# analog_filters.net
KiCad netlist of a schematic drawn in Altium Designer
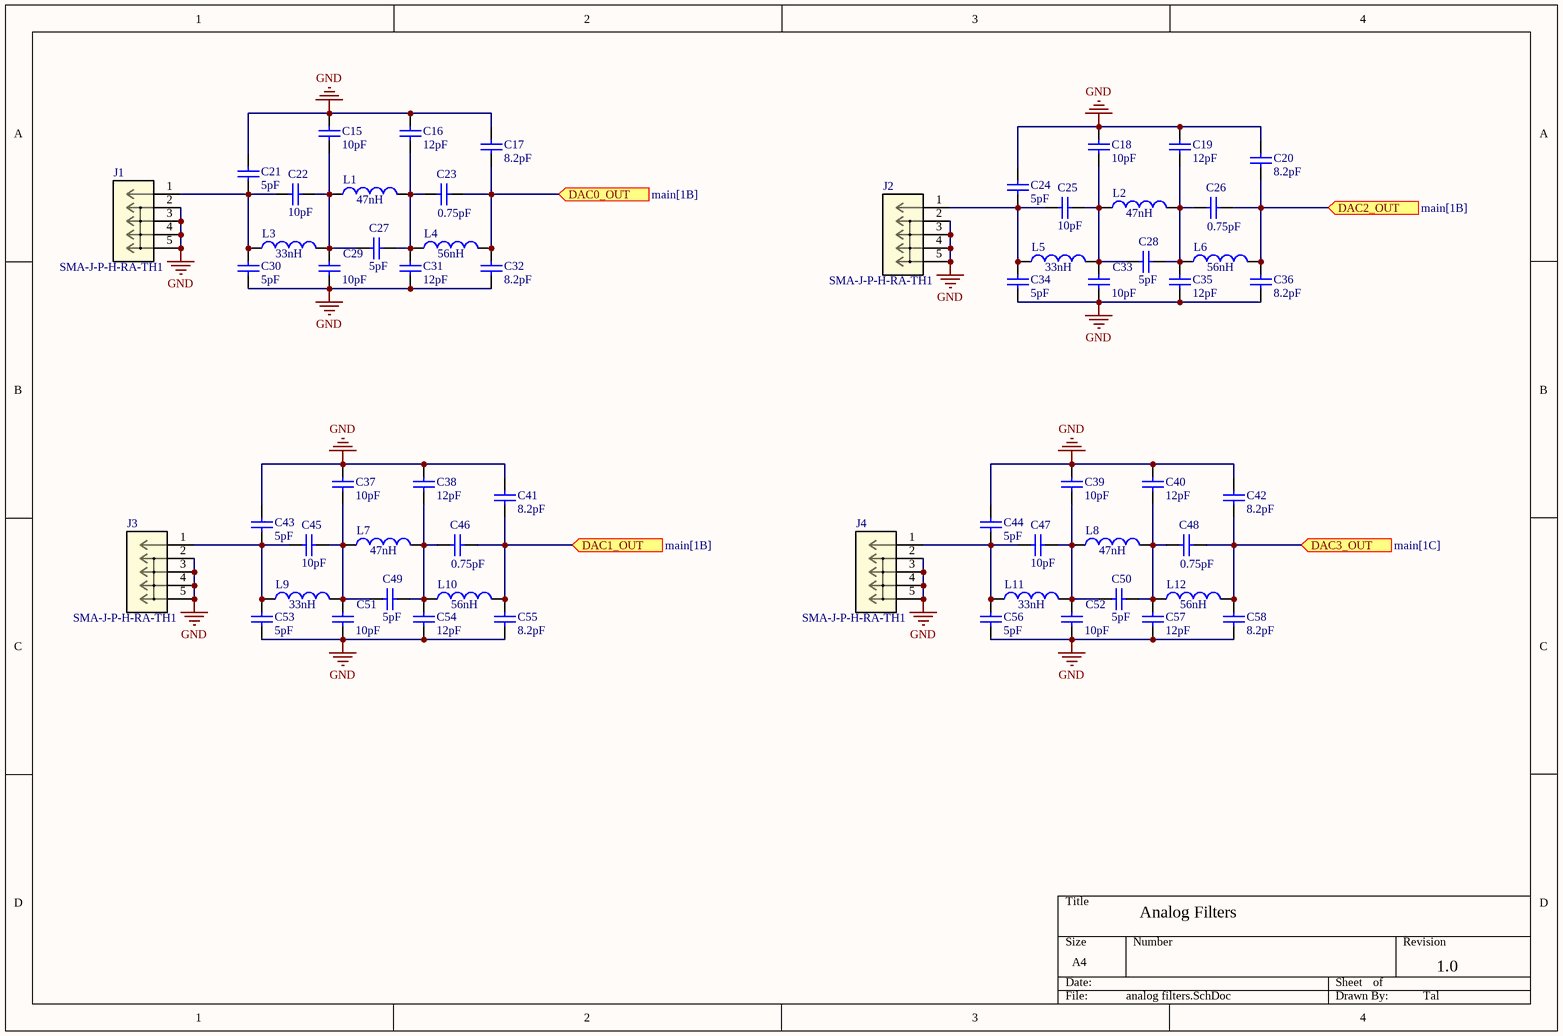
[diagram p0: analog filters.SchDoc]

(export (version "E")
  (design (tool "Eeschema 10.0.6"))
  (components
    (comp (ref "C15")
      (value "10pF 50V")
      (footprint "Landa_PCB:C0402")
      (description "CAP CER 10PF 50V 5% NP0 0402")
      (fields
        (field (name "MANUFACTURER") "TDK Corporation")
        (field (name "MANUFACTURER PART NUMBER") "C1005C0G1H200J")
        (field (name "CAPACITANCE") "10pF")
      )
      (libsource (lib "L_SCH_C") (part "CAP CER 20pF 50V 5% NP0 0402"))
    )
    (comp (ref "C16")
      (value "12pF 50V")
      (footprint "Landa_PCB:C0402")
      (description "CAP CER 12PF 50V 5% NP0 0402")
      (fields
        (field (name "MANUFACTURER") "TDK Corporation")
        (field (name "MANUFACTURER PART NUMBER") "C1005C0G1H200J")
        (field (name "CAPACITANCE") "12pF")
      )
      (libsource (lib "L_SCH_C") (part "CAP CER 20pF 50V 5% NP0 0402"))
    )
    (comp (ref "C17")
      (value "8.2pF 50V")
      (footprint "Landa_PCB:C0402")
      (description "CAP CER 8.2PF 50V 5% NP0 0402")
      (fields
        (field (name "MANUFACTURER") "TDK Corporation")
        (field (name "MANUFACTURER PART NUMBER") "C1005C0G1H200J")
        (field (name "CAPACITANCE") "8.2pF")
      )
      (libsource (lib "L_SCH_C") (part "CAP CER 20pF 50V 5% NP0 0402"))
    )
    (comp (ref "C18")
      (value "10pF 50V")
      (footprint "Landa_PCB:C0402")
      (description "CAP CER 10PF 50V 5% NP0 0402")
      (fields
        (field (name "MANUFACTURER") "TDK Corporation")
        (field (name "MANUFACTURER PART NUMBER") "C1005C0G1H200J")
        (field (name "CAPACITANCE") "10pF")
      )
      (libsource (lib "L_SCH_C") (part "CAP CER 20pF 50V 5% NP0 0402"))
    )
    (comp (ref "C19")
      (value "12pF 50V")
      (footprint "Landa_PCB:C0402")
      (description "CAP CER 12PF 50V 5% NP0 0402")
      (fields
        (field (name "MANUFACTURER") "TDK Corporation")
        (field (name "MANUFACTURER PART NUMBER") "C1005C0G1H200J")
        (field (name "CAPACITANCE") "12pF")
      )
      (libsource (lib "L_SCH_C") (part "CAP CER 20pF 50V 5% NP0 0402"))
    )
    (comp (ref "C20")
      (value "8.2pF 50V")
      (footprint "Landa_PCB:C0402")
      (description "CAP CER 8.2PF 50V 5% NP0 0402")
      (fields
        (field (name "MANUFACTURER") "TDK Corporation")
        (field (name "MANUFACTURER PART NUMBER") "C1005C0G1H200J")
        (field (name "CAPACITANCE") "8.2pF")
      )
      (libsource (lib "L_SCH_C") (part "CAP CER 20pF 50V 5% NP0 0402"))
    )
    (comp (ref "C21")
      (value "5pF 50V")
      (footprint "Landa_PCB:C0402")
      (description "CAP CER 5PF 50V 5% NP0 0402")
      (fields
        (field (name "MANUFACTURER") "TDK Corporation")
        (field (name "MANUFACTURER PART NUMBER") "C1005C0G1H200J")
        (field (name "CAPACITANCE") "5pF")
      )
      (libsource (lib "L_SCH_C") (part "CAP CER 20pF 50V 5% NP0 0402"))
    )
    (comp (ref "C22")
      (value "10pF 50V")
      (footprint "Landa_PCB:C0402")
      (description "CAP CER 10PF 50V 5% NP0 0402")
      (fields
        (field (name "MANUFACTURER") "TDK Corporation")
        (field (name "MANUFACTURER PART NUMBER") "C1005C0G1H200J")
        (field (name "CAPACITANCE") "10pF")
      )
      (libsource (lib "L_SCH_C") (part "CAP CER 20pF 50V 5% NP0 0402"))
    )
    (comp (ref "C23")
      (value "0.75pF 50V")
      (footprint "Landa_PCB:C0402")
      (description "CAP CER 0.75PF 50V 5% NP0 0402")
      (fields
        (field (name "MANUFACTURER") "TDK Corporation")
        (field (name "MANUFACTURER PART NUMBER") "C1005C0G1H200J")
        (field (name "CAPACITANCE") "0.75pF")
      )
      (libsource (lib "L_SCH_C") (part "CAP CER 20pF 50V 5% NP0 0402"))
    )
    (comp (ref "C24")
      (value "5pF 50V")
      (footprint "Landa_PCB:C0402")
      (description "CAP CER 5PF 50V 5% NP0 0402")
      (fields
        (field (name "MANUFACTURER") "TDK Corporation")
        (field (name "MANUFACTURER PART NUMBER") "C1005C0G1H200J")
        (field (name "CAPACITANCE") "5pF")
      )
      (libsource (lib "L_SCH_C") (part "CAP CER 20pF 50V 5% NP0 0402"))
    )
    (comp (ref "C25")
      (value "10pF 50V")
      (footprint "Landa_PCB:C0402")
      (description "CAP CER 10PF 50V 5% NP0 0402")
      (fields
        (field (name "MANUFACTURER") "TDK Corporation")
        (field (name "MANUFACTURER PART NUMBER") "C1005C0G1H200J")
        (field (name "CAPACITANCE") "10pF")
      )
      (libsource (lib "L_SCH_C") (part "CAP CER 20pF 50V 5% NP0 0402"))
    )
    (comp (ref "C26")
      (value "0.75pF 50V")
      (footprint "Landa_PCB:C0402")
      (description "CAP CER 0.75PF 50V 5% NP0 0402")
      (fields
        (field (name "MANUFACTURER") "TDK Corporation")
        (field (name "MANUFACTURER PART NUMBER") "C1005C0G1H200J")
        (field (name "CAPACITANCE") "0.75pF")
      )
      (libsource (lib "L_SCH_C") (part "CAP CER 20pF 50V 5% NP0 0402"))
    )
    (comp (ref "C27")
      (value "5pF 50V")
      (footprint "Landa_PCB:C0402")
      (description "CAP CER 5PF 50V 5% NP0 0402")
      (fields
        (field (name "MANUFACTURER") "TDK Corporation")
        (field (name "MANUFACTURER PART NUMBER") "C1005C0G1H200J")
        (field (name "CAPACITANCE") "5pF")
      )
      (libsource (lib "L_SCH_C") (part "CAP CER 20pF 50V 5% NP0 0402"))
    )
    (comp (ref "C28")
      (value "5pF 50V")
      (footprint "Landa_PCB:C0402")
      (description "CAP CER 5PF 50V 5% NP0 0402")
      (fields
        (field (name "MANUFACTURER") "TDK Corporation")
        (field (name "MANUFACTURER PART NUMBER") "C1005C0G1H200J")
        (field (name "CAPACITANCE") "5pF")
      )
      (libsource (lib "L_SCH_C") (part "CAP CER 20pF 50V 5% NP0 0402"))
    )
    (comp (ref "C29")
      (value "10pF 50V")
      (footprint "Landa_PCB:C0402")
      (description "CAP CER 10PF 50V 5% NP0 0402")
      (fields
        (field (name "MANUFACTURER") "TDK Corporation")
        (field (name "MANUFACTURER PART NUMBER") "C1005C0G1H200J")
        (field (name "CAPACITANCE") "10pF")
      )
      (libsource (lib "L_SCH_C") (part "CAP CER 20pF 50V 5% NP0 0402"))
    )
    (comp (ref "C30")
      (value "5pF 50V")
      (footprint "Landa_PCB:C0402")
      (description "CAP CER 5PF 50V 5% NP0 0402")
      (fields
        (field (name "MANUFACTURER") "TDK Corporation")
        (field (name "MANUFACTURER PART NUMBER") "C1005C0G1H200J")
        (field (name "CAPACITANCE") "5pF")
      )
      (libsource (lib "L_SCH_C") (part "CAP CER 20pF 50V 5% NP0 0402"))
    )
    (comp (ref "C31")
      (value "12pF 50V")
      (footprint "Landa_PCB:C0402")
      (description "CAP CER 12PF 50V 5% NP0 0402")
      (fields
        (field (name "MANUFACTURER") "TDK Corporation")
        (field (name "MANUFACTURER PART NUMBER") "C1005C0G1H200J")
        (field (name "CAPACITANCE") "12pF")
      )
      (libsource (lib "L_SCH_C") (part "CAP CER 20pF 50V 5% NP0 0402"))
    )
    (comp (ref "C32")
      (value "8.2pF 50V")
      (footprint "Landa_PCB:C0402")
      (description "CAP CER 8.2PF 50V 5% NP0 0402")
      (fields
        (field (name "MANUFACTURER") "TDK Corporation")
        (field (name "MANUFACTURER PART NUMBER") "C1005C0G1H200J")
        (field (name "CAPACITANCE") "8.2pF")
      )
      (libsource (lib "L_SCH_C") (part "CAP CER 20pF 50V 5% NP0 0402"))
    )
    (comp (ref "C33")
      (value "10pF 50V")
      (footprint "Landa_PCB:C0402")
      (description "CAP CER 10PF 50V 5% NP0 0402")
      (fields
        (field (name "MANUFACTURER") "TDK Corporation")
        (field (name "MANUFACTURER PART NUMBER") "C1005C0G1H200J")
        (field (name "CAPACITANCE") "10pF")
      )
      (libsource (lib "L_SCH_C") (part "CAP CER 20pF 50V 5% NP0 0402"))
    )
    (comp (ref "C34")
      (value "5pF 50V")
      (footprint "Landa_PCB:C0402")
      (description "CAP CER 5PF 50V 5% NP0 0402")
      (fields
        (field (name "MANUFACTURER") "TDK Corporation")
        (field (name "MANUFACTURER PART NUMBER") "C1005C0G1H200J")
        (field (name "CAPACITANCE") "5pF")
      )
      (libsource (lib "L_SCH_C") (part "CAP CER 20pF 50V 5% NP0 0402"))
    )
    (comp (ref "C35")
      (value "12pF 50V")
      (footprint "Landa_PCB:C0402")
      (description "CAP CER 12PF 50V 5% NP0 0402")
      (fields
        (field (name "MANUFACTURER") "TDK Corporation")
        (field (name "MANUFACTURER PART NUMBER") "C1005C0G1H200J")
        (field (name "CAPACITANCE") "12pF")
      )
      (libsource (lib "L_SCH_C") (part "CAP CER 20pF 50V 5% NP0 0402"))
    )
    (comp (ref "C36")
      (value "8.2pF 50V")
      (footprint "Landa_PCB:C0402")
      (description "CAP CER 8.2PF 50V 5% NP0 0402")
      (fields
        (field (name "MANUFACTURER") "TDK Corporation")
        (field (name "MANUFACTURER PART NUMBER") "C1005C0G1H200J")
        (field (name "CAPACITANCE") "8.2pF")
      )
      (libsource (lib "L_SCH_C") (part "CAP CER 20pF 50V 5% NP0 0402"))
    )
    (comp (ref "C37")
      (value "10pF 50V")
      (footprint "Landa_PCB:C0402")
      (description "CAP CER 10PF 50V 5% NP0 0402")
      (fields
        (field (name "MANUFACTURER") "TDK Corporation")
        (field (name "MANUFACTURER PART NUMBER") "C1005C0G1H200J")
        (field (name "CAPACITANCE") "10pF")
      )
      (libsource (lib "L_SCH_C") (part "CAP CER 20pF 50V 5% NP0 0402"))
    )
    (comp (ref "C38")
      (value "12pF 50V")
      (footprint "Landa_PCB:C0402")
      (description "CAP CER 12PF 50V 5% NP0 0402")
      (fields
        (field (name "MANUFACTURER") "TDK Corporation")
        (field (name "MANUFACTURER PART NUMBER") "C1005C0G1H200J")
        (field (name "CAPACITANCE") "12pF")
      )
      (libsource (lib "L_SCH_C") (part "CAP CER 20pF 50V 5% NP0 0402"))
    )
    (comp (ref "C39")
      (value "10pF 50V")
      (footprint "Landa_PCB:C0402")
      (description "CAP CER 10PF 50V 5% NP0 0402")
      (fields
        (field (name "MANUFACTURER") "TDK Corporation")
        (field (name "MANUFACTURER PART NUMBER") "C1005C0G1H200J")
        (field (name "CAPACITANCE") "10pF")
      )
      (libsource (lib "L_SCH_C") (part "CAP CER 20pF 50V 5% NP0 0402"))
    )
    (comp (ref "C40")
      (value "12pF 50V")
      (footprint "Landa_PCB:C0402")
      (description "CAP CER 12PF 50V 5% NP0 0402")
      (fields
        (field (name "MANUFACTURER") "TDK Corporation")
        (field (name "MANUFACTURER PART NUMBER") "C1005C0G1H200J")
        (field (name "CAPACITANCE") "12pF")
      )
      (libsource (lib "L_SCH_C") (part "CAP CER 20pF 50V 5% NP0 0402"))
    )
    (comp (ref "C41")
      (value "8.2pF 50V")
      (footprint "Landa_PCB:C0402")
      (description "CAP CER 8.2PF 50V 5% NP0 0402")
      (fields
        (field (name "MANUFACTURER") "TDK Corporation")
        (field (name "MANUFACTURER PART NUMBER") "C1005C0G1H200J")
        (field (name "CAPACITANCE") "8.2pF")
      )
      (libsource (lib "L_SCH_C") (part "CAP CER 20pF 50V 5% NP0 0402"))
    )
    (comp (ref "C42")
      (value "8.2pF 50V")
      (footprint "Landa_PCB:C0402")
      (description "CAP CER 8.2PF 50V 5% NP0 0402")
      (fields
        (field (name "MANUFACTURER") "TDK Corporation")
        (field (name "MANUFACTURER PART NUMBER") "C1005C0G1H200J")
        (field (name "CAPACITANCE") "8.2pF")
      )
      (libsource (lib "L_SCH_C") (part "CAP CER 20pF 50V 5% NP0 0402"))
    )
    (comp (ref "C43")
      (value "5pF 50V")
      (footprint "Landa_PCB:C0402")
      (description "CAP CER 5PF 50V 5% NP0 0402")
      (fields
        (field (name "MANUFACTURER") "TDK Corporation")
        (field (name "MANUFACTURER PART NUMBER") "C1005C0G1H200J")
        (field (name "CAPACITANCE") "5pF")
      )
      (libsource (lib "L_SCH_C") (part "CAP CER 20pF 50V 5% NP0 0402"))
    )
    (comp (ref "C44")
      (value "5pF 50V")
      (footprint "Landa_PCB:C0402")
      (description "CAP CER 5PF 50V 5% NP0 0402")
      (fields
        (field (name "MANUFACTURER") "TDK Corporation")
        (field (name "MANUFACTURER PART NUMBER") "C1005C0G1H200J")
        (field (name "CAPACITANCE") "5pF")
      )
      (libsource (lib "L_SCH_C") (part "CAP CER 20pF 50V 5% NP0 0402"))
    )
    (comp (ref "C45")
      (value "10pF 50V")
      (footprint "Landa_PCB:C0402")
      (description "CAP CER 10PF 50V 5% NP0 0402")
      (fields
        (field (name "MANUFACTURER") "TDK Corporation")
        (field (name "MANUFACTURER PART NUMBER") "C1005C0G1H200J")
        (field (name "CAPACITANCE") "10pF")
      )
      (libsource (lib "L_SCH_C") (part "CAP CER 20pF 50V 5% NP0 0402"))
    )
    (comp (ref "C46")
      (value "0.75pF 50V")
      (footprint "Landa_PCB:C0402")
      (description "CAP CER 0.75PF 50V 5% NP0 0402")
      (fields
        (field (name "MANUFACTURER") "TDK Corporation")
        (field (name "MANUFACTURER PART NUMBER") "C1005C0G1H200J")
        (field (name "CAPACITANCE") "0.75pF")
      )
      (libsource (lib "L_SCH_C") (part "CAP CER 20pF 50V 5% NP0 0402"))
    )
    (comp (ref "C47")
      (value "10pF 50V")
      (footprint "Landa_PCB:C0402")
      (description "CAP CER 10PF 50V 5% NP0 0402")
      (fields
        (field (name "MANUFACTURER") "TDK Corporation")
        (field (name "MANUFACTURER PART NUMBER") "C1005C0G1H200J")
        (field (name "CAPACITANCE") "10pF")
      )
      (libsource (lib "L_SCH_C") (part "CAP CER 20pF 50V 5% NP0 0402"))
    )
    (comp (ref "C48")
      (value "0.75pF 50V")
      (footprint "Landa_PCB:C0402")
      (description "CAP CER 0.75PF 50V 5% NP0 0402")
      (fields
        (field (name "MANUFACTURER") "TDK Corporation")
        (field (name "MANUFACTURER PART NUMBER") "C1005C0G1H200J")
        (field (name "CAPACITANCE") "0.75pF")
      )
      (libsource (lib "L_SCH_C") (part "CAP CER 20pF 50V 5% NP0 0402"))
    )
    (comp (ref "C49")
      (value "5pF 50V")
      (footprint "Landa_PCB:C0402")
      (description "CAP CER 5PF 50V 5% NP0 0402")
      (fields
        (field (name "MANUFACTURER") "TDK Corporation")
        (field (name "MANUFACTURER PART NUMBER") "C1005C0G1H200J")
        (field (name "CAPACITANCE") "5pF")
      )
      (libsource (lib "L_SCH_C") (part "CAP CER 20pF 50V 5% NP0 0402"))
    )
    (comp (ref "C50")
      (value "5pF 50V")
      (footprint "Landa_PCB:C0402")
      (description "CAP CER 5PF 50V 5% NP0 0402")
      (fields
        (field (name "MANUFACTURER") "TDK Corporation")
        (field (name "MANUFACTURER PART NUMBER") "C1005C0G1H200J")
        (field (name "CAPACITANCE") "5pF")
      )
      (libsource (lib "L_SCH_C") (part "CAP CER 20pF 50V 5% NP0 0402"))
    )
    (comp (ref "C51")
      (value "10pF 50V")
      (footprint "Landa_PCB:C0402")
      (description "CAP CER 10PF 50V 5% NP0 0402")
      (fields
        (field (name "MANUFACTURER") "TDK Corporation")
        (field (name "MANUFACTURER PART NUMBER") "C1005C0G1H200J")
        (field (name "CAPACITANCE") "10pF")
      )
      (libsource (lib "L_SCH_C") (part "CAP CER 20pF 50V 5% NP0 0402"))
    )
    (comp (ref "C52")
      (value "10pF 50V")
      (footprint "Landa_PCB:C0402")
      (description "CAP CER 10PF 50V 5% NP0 0402")
      (fields
        (field (name "MANUFACTURER") "TDK Corporation")
        (field (name "MANUFACTURER PART NUMBER") "C1005C0G1H200J")
        (field (name "CAPACITANCE") "10pF")
      )
      (libsource (lib "L_SCH_C") (part "CAP CER 20pF 50V 5% NP0 0402"))
    )
    (comp (ref "C53")
      (value "5pF 50V")
      (footprint "Landa_PCB:C0402")
      (description "CAP CER 5PF 50V 5% NP0 0402")
      (fields
        (field (name "MANUFACTURER") "TDK Corporation")
        (field (name "MANUFACTURER PART NUMBER") "C1005C0G1H200J")
        (field (name "CAPACITANCE") "5pF")
      )
      (libsource (lib "L_SCH_C") (part "CAP CER 20pF 50V 5% NP0 0402"))
    )
    (comp (ref "C54")
      (value "12pF 50V")
      (footprint "Landa_PCB:C0402")
      (description "CAP CER 12PF 50V 5% NP0 0402")
      (fields
        (field (name "MANUFACTURER") "TDK Corporation")
        (field (name "MANUFACTURER PART NUMBER") "C1005C0G1H200J")
        (field (name "CAPACITANCE") "12pF")
      )
      (libsource (lib "L_SCH_C") (part "CAP CER 20pF 50V 5% NP0 0402"))
    )
    (comp (ref "C55")
      (value "8.2pF 50V")
      (footprint "Landa_PCB:C0402")
      (description "CAP CER 8.2PF 50V 5% NP0 0402")
      (fields
        (field (name "MANUFACTURER") "TDK Corporation")
        (field (name "MANUFACTURER PART NUMBER") "C1005C0G1H200J")
        (field (name "CAPACITANCE") "8.2pF")
      )
      (libsource (lib "L_SCH_C") (part "CAP CER 20pF 50V 5% NP0 0402"))
    )
    (comp (ref "C56")
      (value "5pF 50V")
      (footprint "Landa_PCB:C0402")
      (description "CAP CER 5PF 50V 5% NP0 0402")
      (fields
        (field (name "MANUFACTURER") "TDK Corporation")
        (field (name "MANUFACTURER PART NUMBER") "C1005C0G1H200J")
        (field (name "CAPACITANCE") "5pF")
      )
      (libsource (lib "L_SCH_C") (part "CAP CER 20pF 50V 5% NP0 0402"))
    )
    (comp (ref "C57")
      (value "12pF 50V")
      (footprint "Landa_PCB:C0402")
      (description "CAP CER 12PF 50V 5% NP0 0402")
      (fields
        (field (name "MANUFACTURER") "TDK Corporation")
        (field (name "MANUFACTURER PART NUMBER") "C1005C0G1H200J")
        (field (name "CAPACITANCE") "12pF")
      )
      (libsource (lib "L_SCH_C") (part "CAP CER 20pF 50V 5% NP0 0402"))
    )
    (comp (ref "C58")
      (value "8.2pF 50V")
      (footprint "Landa_PCB:C0402")
      (description "CAP CER 8.2PF 50V 5% NP0 0402")
      (fields
        (field (name "MANUFACTURER") "TDK Corporation")
        (field (name "MANUFACTURER PART NUMBER") "C1005C0G1H200J")
        (field (name "CAPACITANCE") "8.2pF")
      )
      (libsource (lib "L_SCH_C") (part "CAP CER 20pF 50V 5% NP0 0402"))
    )
    (comp (ref "J1")
      (value "SMA-J-P-H-RA-TH1")
      (footprint "CONN_SMA-J-P-H-RA-TH1_SAI")
      (description "No Description Available")
      (fields (field (name "COPYRIGHT") "Copyright (C) 2023 Ultra Librarian. All rights reserved."))
      (libsource (lib "SMA-J-P-H-RA-TH1") (part "SMA-J-P-H-RA-TH1"))
    )
    (comp (ref "J2")
      (value "SMA-J-P-H-RA-TH1")
      (footprint "CONN_SMA-J-P-H-RA-TH1_SAI")
      (description "No Description Available")
      (fields (field (name "COPYRIGHT") "Copyright (C) 2023 Ultra Librarian. All rights reserved."))
      (libsource (lib "SMA-J-P-H-RA-TH1") (part "SMA-J-P-H-RA-TH1"))
    )
    (comp (ref "J3")
      (value "SMA-J-P-H-RA-TH1")
      (footprint "CONN_SMA-J-P-H-RA-TH1_SAI")
      (description "No Description Available")
      (fields (field (name "COPYRIGHT") "Copyright (C) 2023 Ultra Librarian. All rights reserved."))
      (libsource (lib "SMA-J-P-H-RA-TH1") (part "SMA-J-P-H-RA-TH1"))
    )
    (comp (ref "J4")
      (value "SMA-J-P-H-RA-TH1")
      (footprint "CONN_SMA-J-P-H-RA-TH1_SAI")
      (description "No Description Available")
      (fields (field (name "COPYRIGHT") "Copyright (C) 2023 Ultra Librarian. All rights reserved."))
      (libsource (lib "SMA-J-P-H-RA-TH1") (part "SMA-J-P-H-RA-TH1"))
    )
    (comp (ref "L1")
      (value "47nH")
      (footprint "0402-A")
      (description "Inductor")
      (fields (field (name "PUBLISHER") "Altium Limited"))
      (libsource (lib "Miscellaneous Devices") (part "Inductor"))
    )
    (comp (ref "L2")
      (value "47nH")
      (footprint "0402-A")
      (description "Inductor")
      (fields (field (name "PUBLISHER") "Altium Limited"))
      (libsource (lib "Miscellaneous Devices") (part "Inductor"))
    )
    (comp (ref "L3")
      (value "33nH")
      (footprint "0402-A")
      (description "Inductor")
      (fields (field (name "PUBLISHER") "Altium Limited"))
      (libsource (lib "Miscellaneous Devices") (part "Inductor"))
    )
    (comp (ref "L4")
      (value "56nH")
      (footprint "0402-A")
      (description "Inductor")
      (fields (field (name "PUBLISHER") "Altium Limited"))
      (libsource (lib "Miscellaneous Devices") (part "Inductor"))
    )
    (comp (ref "L5")
      (value "33nH")
      (footprint "0402-A")
      (description "Inductor")
      (fields (field (name "PUBLISHER") "Altium Limited"))
      (libsource (lib "Miscellaneous Devices") (part "Inductor"))
    )
    (comp (ref "L6")
      (value "56nH")
      (footprint "0402-A")
      (description "Inductor")
      (fields (field (name "PUBLISHER") "Altium Limited"))
      (libsource (lib "Miscellaneous Devices") (part "Inductor"))
    )
    (comp (ref "L7")
      (value "47nH")
      (footprint "0402-A")
      (description "Inductor")
      (fields (field (name "PUBLISHER") "Altium Limited"))
      (libsource (lib "Miscellaneous Devices") (part "Inductor"))
    )
    (comp (ref "L8")
      (value "47nH")
      (footprint "0402-A")
      (description "Inductor")
      (fields (field (name "PUBLISHER") "Altium Limited"))
      (libsource (lib "Miscellaneous Devices") (part "Inductor"))
    )
    (comp (ref "L9")
      (value "33nH")
      (footprint "0402-A")
      (description "Inductor")
      (fields (field (name "PUBLISHER") "Altium Limited"))
      (libsource (lib "Miscellaneous Devices") (part "Inductor"))
    )
    (comp (ref "L10")
      (value "56nH")
      (footprint "0402-A")
      (description "Inductor")
      (fields (field (name "PUBLISHER") "Altium Limited"))
      (libsource (lib "Miscellaneous Devices") (part "Inductor"))
    )
    (comp (ref "L11")
      (value "33nH")
      (footprint "0402-A")
      (description "Inductor")
      (fields (field (name "PUBLISHER") "Altium Limited"))
      (libsource (lib "Miscellaneous Devices") (part "Inductor"))
    )
    (comp (ref "L12")
      (value "56nH")
      (footprint "0402-A")
      (description "Inductor")
      (fields (field (name "PUBLISHER") "Altium Limited"))
      (libsource (lib "Miscellaneous Devices") (part "Inductor"))
    )
  )
  (nets
    (net (code "1") (name "/DAC0_OUT") (class "Default")
      (node (ref "C17") (pin "1") (pinfunction "1_1") (pintype "passive"))
      (node (ref "C23") (pin "2") (pinfunction "2_2") (pintype "passive"))
      (node (ref "C32") (pin "2") (pinfunction "2_2") (pintype "passive"))
      (node (ref "L4") (pin "2") (pinfunction "2_2") (pintype "passive"))
    )
    (net (code "2") (name "/DAC1_OUT") (class "Default")
      (node (ref "C41") (pin "1") (pinfunction "1_1") (pintype "passive"))
      (node (ref "C46") (pin "2") (pinfunction "2_2") (pintype "passive"))
      (node (ref "C55") (pin "2") (pinfunction "2_2") (pintype "passive"))
      (node (ref "L10") (pin "2") (pinfunction "2_2") (pintype "passive"))
    )
    (net (code "3") (name "/DAC2_OUT") (class "Default")
      (node (ref "C20") (pin "1") (pinfunction "1_1") (pintype "passive"))
      (node (ref "C26") (pin "2") (pinfunction "2_2") (pintype "passive"))
      (node (ref "C36") (pin "2") (pinfunction "2_2") (pintype "passive"))
      (node (ref "L6") (pin "2") (pinfunction "2_2") (pintype "passive"))
    )
    (net (code "4") (name "/DAC3_OUT") (class "Default")
      (node (ref "C42") (pin "1") (pinfunction "1_1") (pintype "passive"))
      (node (ref "C48") (pin "2") (pinfunction "2_2") (pintype "passive"))
      (node (ref "C58") (pin "2") (pinfunction "2_2") (pintype "passive"))
      (node (ref "L12") (pin "2") (pinfunction "2_2") (pintype "passive"))
    )
    (net (code "5") (name "GND") (class "Default")
      (node (ref "C15") (pin "2") (pinfunction "2_2") (pintype "passive"))
      (node (ref "C16") (pin "2") (pinfunction "2_2") (pintype "passive"))
      (node (ref "C17") (pin "2") (pinfunction "2_2") (pintype "passive"))
      (node (ref "C18") (pin "2") (pinfunction "2_2") (pintype "passive"))
      (node (ref "C19") (pin "2") (pinfunction "2_2") (pintype "passive"))
      (node (ref "C20") (pin "2") (pinfunction "2_2") (pintype "passive"))
      (node (ref "C21") (pin "2") (pinfunction "2_2") (pintype "passive"))
      (node (ref "C24") (pin "2") (pinfunction "2_2") (pintype "passive"))
      (node (ref "C29") (pin "1") (pinfunction "1_1") (pintype "passive"))
      (node (ref "C30") (pin "1") (pinfunction "1_1") (pintype "passive"))
      (node (ref "C31") (pin "1") (pinfunction "1_1") (pintype "passive"))
      (node (ref "C32") (pin "1") (pinfunction "1_1") (pintype "passive"))
      (node (ref "C33") (pin "1") (pinfunction "1_1") (pintype "passive"))
      (node (ref "C34") (pin "1") (pinfunction "1_1") (pintype "passive"))
      (node (ref "C35") (pin "1") (pinfunction "1_1") (pintype "passive"))
      (node (ref "C36") (pin "1") (pinfunction "1_1") (pintype "passive"))
      (node (ref "C37") (pin "2") (pinfunction "2_2") (pintype "passive"))
      (node (ref "C38") (pin "2") (pinfunction "2_2") (pintype "passive"))
      (node (ref "C39") (pin "2") (pinfunction "2_2") (pintype "passive"))
      (node (ref "C40") (pin "2") (pinfunction "2_2") (pintype "passive"))
      (node (ref "C41") (pin "2") (pinfunction "2_2") (pintype "passive"))
      (node (ref "C42") (pin "2") (pinfunction "2_2") (pintype "passive"))
      (node (ref "C43") (pin "2") (pinfunction "2_2") (pintype "passive"))
      (node (ref "C44") (pin "2") (pinfunction "2_2") (pintype "passive"))
      (node (ref "C51") (pin "1") (pinfunction "1_1") (pintype "passive"))
      (node (ref "C52") (pin "1") (pinfunction "1_1") (pintype "passive"))
      (node (ref "C53") (pin "1") (pinfunction "1_1") (pintype "passive"))
      (node (ref "C54") (pin "1") (pinfunction "1_1") (pintype "passive"))
      (node (ref "C55") (pin "1") (pinfunction "1_1") (pintype "passive"))
      (node (ref "C56") (pin "1") (pinfunction "1_1") (pintype "passive"))
      (node (ref "C57") (pin "1") (pinfunction "1_1") (pintype "passive"))
      (node (ref "C58") (pin "1") (pinfunction "1_1") (pintype "passive"))
      (node (ref "J1") (pin "2") (pinfunction "2_2") (pintype "passive"))
      (node (ref "J1") (pin "3") (pinfunction "3_3") (pintype "passive"))
      (node (ref "J1") (pin "4") (pinfunction "4_4") (pintype "passive"))
      (node (ref "J1") (pin "5") (pinfunction "5_5") (pintype "passive"))
      (node (ref "J2") (pin "2") (pinfunction "2_2") (pintype "passive"))
      (node (ref "J2") (pin "3") (pinfunction "3_3") (pintype "passive"))
      (node (ref "J2") (pin "4") (pinfunction "4_4") (pintype "passive"))
      (node (ref "J2") (pin "5") (pinfunction "5_5") (pintype "passive"))
      (node (ref "J3") (pin "2") (pinfunction "2_2") (pintype "passive"))
      (node (ref "J3") (pin "3") (pinfunction "3_3") (pintype "passive"))
      (node (ref "J3") (pin "4") (pinfunction "4_4") (pintype "passive"))
      (node (ref "J3") (pin "5") (pinfunction "5_5") (pintype "passive"))
      (node (ref "J4") (pin "2") (pinfunction "2_2") (pintype "passive"))
      (node (ref "J4") (pin "3") (pinfunction "3_3") (pintype "passive"))
      (node (ref "J4") (pin "4") (pinfunction "4_4") (pintype "passive"))
      (node (ref "J4") (pin "5") (pinfunction "5_5") (pintype "passive"))
    )
    (net (code "6") (name "Net-(C15-Pad1)") (class "Default")
      (node (ref "C15") (pin "1") (pinfunction "1_1") (pintype "passive"))
      (node (ref "C22") (pin "1") (pinfunction "1_1") (pintype "passive"))
      (node (ref "C27") (pin "2") (pinfunction "2_2") (pintype "passive"))
      (node (ref "C29") (pin "2") (pinfunction "2_2") (pintype "passive"))
      (node (ref "L1") (pin "1") (pinfunction "1_1") (pintype "passive"))
      (node (ref "L3") (pin "2") (pinfunction "2_2") (pintype "passive"))
    )
    (net (code "7") (name "Net-(C16-Pad1)") (class "Default")
      (node (ref "C16") (pin "1") (pinfunction "1_1") (pintype "passive"))
      (node (ref "C23") (pin "1") (pinfunction "1_1") (pintype "passive"))
      (node (ref "C27") (pin "1") (pinfunction "1_1") (pintype "passive"))
      (node (ref "C31") (pin "2") (pinfunction "2_2") (pintype "passive"))
      (node (ref "L1") (pin "2") (pinfunction "2_2") (pintype "passive"))
      (node (ref "L4") (pin "1") (pinfunction "1_1") (pintype "passive"))
    )
    (net (code "8") (name "Net-(C18-Pad1)") (class "Default")
      (node (ref "C18") (pin "1") (pinfunction "1_1") (pintype "passive"))
      (node (ref "C25") (pin "1") (pinfunction "1_1") (pintype "passive"))
      (node (ref "C28") (pin "2") (pinfunction "2_2") (pintype "passive"))
      (node (ref "C33") (pin "2") (pinfunction "2_2") (pintype "passive"))
      (node (ref "L2") (pin "1") (pinfunction "1_1") (pintype "passive"))
      (node (ref "L5") (pin "2") (pinfunction "2_2") (pintype "passive"))
    )
    (net (code "9") (name "Net-(C19-Pad1)") (class "Default")
      (node (ref "C19") (pin "1") (pinfunction "1_1") (pintype "passive"))
      (node (ref "C26") (pin "1") (pinfunction "1_1") (pintype "passive"))
      (node (ref "C28") (pin "1") (pinfunction "1_1") (pintype "passive"))
      (node (ref "C35") (pin "2") (pinfunction "2_2") (pintype "passive"))
      (node (ref "L2") (pin "2") (pinfunction "2_2") (pintype "passive"))
      (node (ref "L6") (pin "1") (pinfunction "1_1") (pintype "passive"))
    )
    (net (code "10") (name "Net-(C21-Pad1)") (class "Default")
      (node (ref "C21") (pin "1") (pinfunction "1_1") (pintype "passive"))
      (node (ref "C22") (pin "2") (pinfunction "2_2") (pintype "passive"))
      (node (ref "C30") (pin "2") (pinfunction "2_2") (pintype "passive"))
      (node (ref "J1") (pin "1") (pinfunction "1_1") (pintype "passive"))
      (node (ref "L3") (pin "1") (pinfunction "1_1") (pintype "passive"))
    )
    (net (code "11") (name "Net-(C24-Pad1)") (class "Default")
      (node (ref "C24") (pin "1") (pinfunction "1_1") (pintype "passive"))
      (node (ref "C25") (pin "2") (pinfunction "2_2") (pintype "passive"))
      (node (ref "C34") (pin "2") (pinfunction "2_2") (pintype "passive"))
      (node (ref "J2") (pin "1") (pinfunction "1_1") (pintype "passive"))
      (node (ref "L5") (pin "1") (pinfunction "1_1") (pintype "passive"))
    )
    (net (code "12") (name "Net-(C37-Pad1)") (class "Default")
      (node (ref "C37") (pin "1") (pinfunction "1_1") (pintype "passive"))
      (node (ref "C45") (pin "1") (pinfunction "1_1") (pintype "passive"))
      (node (ref "C49") (pin "2") (pinfunction "2_2") (pintype "passive"))
      (node (ref "C51") (pin "2") (pinfunction "2_2") (pintype "passive"))
      (node (ref "L7") (pin "1") (pinfunction "1_1") (pintype "passive"))
      (node (ref "L9") (pin "2") (pinfunction "2_2") (pintype "passive"))
    )
    (net (code "13") (name "Net-(C38-Pad1)") (class "Default")
      (node (ref "C38") (pin "1") (pinfunction "1_1") (pintype "passive"))
      (node (ref "C46") (pin "1") (pinfunction "1_1") (pintype "passive"))
      (node (ref "C49") (pin "1") (pinfunction "1_1") (pintype "passive"))
      (node (ref "C54") (pin "2") (pinfunction "2_2") (pintype "passive"))
      (node (ref "L10") (pin "1") (pinfunction "1_1") (pintype "passive"))
      (node (ref "L7") (pin "2") (pinfunction "2_2") (pintype "passive"))
    )
    (net (code "14") (name "Net-(C39-Pad1)") (class "Default")
      (node (ref "C39") (pin "1") (pinfunction "1_1") (pintype "passive"))
      (node (ref "C47") (pin "1") (pinfunction "1_1") (pintype "passive"))
      (node (ref "C50") (pin "2") (pinfunction "2_2") (pintype "passive"))
      (node (ref "C52") (pin "2") (pinfunction "2_2") (pintype "passive"))
      (node (ref "L11") (pin "2") (pinfunction "2_2") (pintype "passive"))
      (node (ref "L8") (pin "1") (pinfunction "1_1") (pintype "passive"))
    )
    (net (code "15") (name "Net-(C40-Pad1)") (class "Default")
      (node (ref "C40") (pin "1") (pinfunction "1_1") (pintype "passive"))
      (node (ref "C48") (pin "1") (pinfunction "1_1") (pintype "passive"))
      (node (ref "C50") (pin "1") (pinfunction "1_1") (pintype "passive"))
      (node (ref "C57") (pin "2") (pinfunction "2_2") (pintype "passive"))
      (node (ref "L12") (pin "1") (pinfunction "1_1") (pintype "passive"))
      (node (ref "L8") (pin "2") (pinfunction "2_2") (pintype "passive"))
    )
    (net (code "16") (name "Net-(C43-Pad1)") (class "Default")
      (node (ref "C43") (pin "1") (pinfunction "1_1") (pintype "passive"))
      (node (ref "C45") (pin "2") (pinfunction "2_2") (pintype "passive"))
      (node (ref "C53") (pin "2") (pinfunction "2_2") (pintype "passive"))
      (node (ref "J3") (pin "1") (pinfunction "1_1") (pintype "passive"))
      (node (ref "L9") (pin "1") (pinfunction "1_1") (pintype "passive"))
    )
    (net (code "17") (name "Net-(C44-Pad1)") (class "Default")
      (node (ref "C44") (pin "1") (pinfunction "1_1") (pintype "passive"))
      (node (ref "C47") (pin "2") (pinfunction "2_2") (pintype "passive"))
      (node (ref "C56") (pin "2") (pinfunction "2_2") (pintype "passive"))
      (node (ref "J4") (pin "1") (pinfunction "1_1") (pintype "passive"))
      (node (ref "L11") (pin "1") (pinfunction "1_1") (pintype "passive"))
    )
  )
)
